# hb100_smd.net
KiCad netlist of a schematic drawn in EAGLE
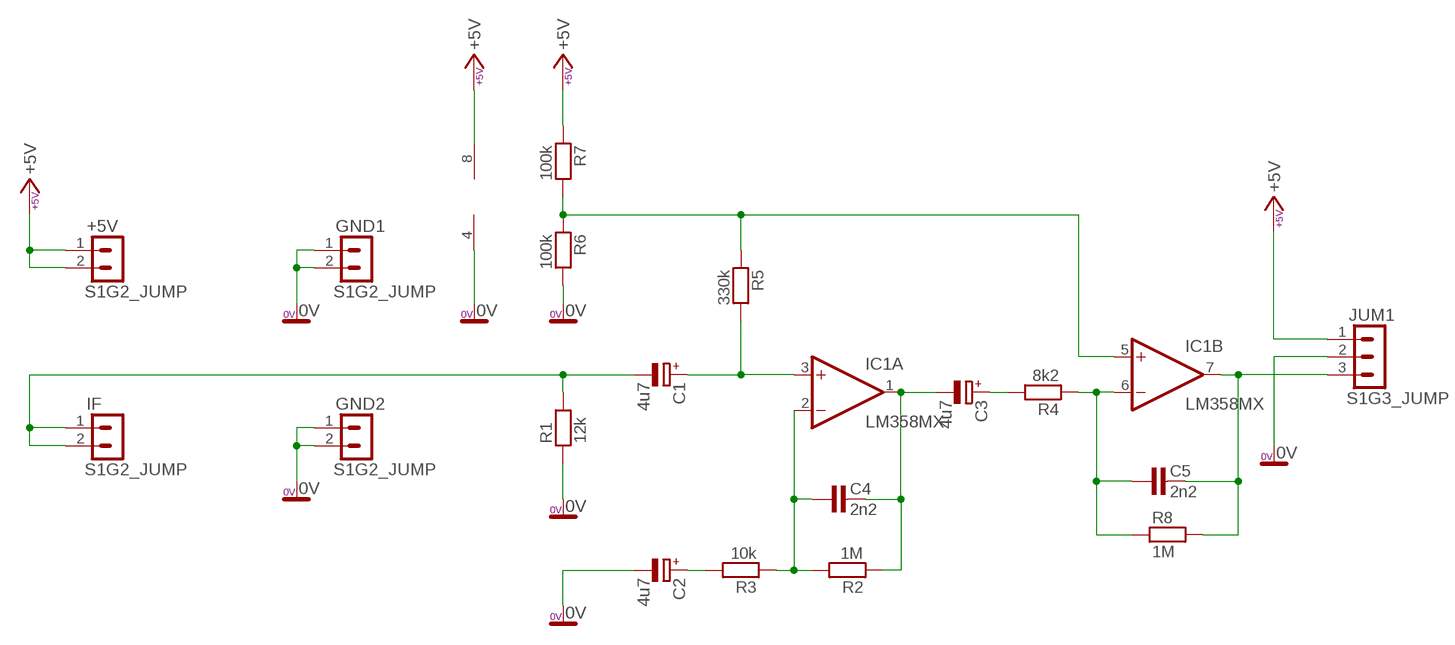
[diagram p0: schematic, sheet 1]

(export (version "E")
  (design (tool "Eeschema 10.0.6"))
  (components
    (comp (ref "+5V")
      (value "S1G2_JUMP")
      (footprint "eagle-import:S1G2_JUM")
      (libsource (lib "eagle-import") (part "S1G2_JUMP"))
    )
    (comp (ref "C1")
      (value "4u7")
      (footprint "eagle-import:SMC_A")
      (libsource (lib "eagle-import") (part "CPOL-EUSMCA"))
    )
    (comp (ref "C2")
      (value "4u7")
      (footprint "eagle-import:SMC_A")
      (libsource (lib "eagle-import") (part "CPOL-EUSMCA"))
    )
    (comp (ref "C3")
      (value "4u7")
      (footprint "eagle-import:SMC_A")
      (libsource (lib "eagle-import") (part "CPOL-EUSMCA"))
    )
    (comp (ref "C4")
      (value "2n2")
      (footprint "eagle-import:0805")
      (libsource (lib "eagle-import") (part "C-KERAMIK_SMD_0805"))
    )
    (comp (ref "C5")
      (value "2n2")
      (footprint "eagle-import:0805")
      (libsource (lib "eagle-import") (part "C-KERAMIK_SMD_0805"))
    )
    (comp (ref "GND1")
      (value "S1G2_JUMP")
      (footprint "eagle-import:S1G2_JUM")
      (libsource (lib "eagle-import") (part "S1G2_JUMP"))
    )
    (comp (ref "GND2")
      (value "S1G2_JUMP")
      (footprint "eagle-import:S1G2_JUM")
      (libsource (lib "eagle-import") (part "S1G2_JUMP"))
    )
    (comp (ref "IC1")
      (value "LM358MX")
      (footprint "eagle-import:SO08")
      (libsource (lib "eagle-import") (part "LM358MX"))
    )
    (comp (ref "IF")
      (value "S1G2_JUMP")
      (footprint "eagle-import:S1G2_JUM")
      (libsource (lib "eagle-import") (part "S1G2_JUMP"))
    )
    (comp (ref "JUM1")
      (value "S1G3_JUMP")
      (footprint "eagle-import:S1G3_JUM")
      (libsource (lib "eagle-import") (part "S1G3_JUMP"))
    )
    (comp (ref "R1")
      (value "12k")
      (footprint "eagle-import:0805")
      (libsource (lib "eagle-import") (part "R_SMD_0805"))
    )
    (comp (ref "R2")
      (value "1M")
      (footprint "eagle-import:0805")
      (libsource (lib "eagle-import") (part "R_SMD_0805"))
    )
    (comp (ref "R3")
      (value "10k")
      (footprint "eagle-import:0805")
      (libsource (lib "eagle-import") (part "R_SMD_0805"))
    )
    (comp (ref "R4")
      (value "8k2")
      (footprint "eagle-import:0805")
      (libsource (lib "eagle-import") (part "R_SMD_0805"))
    )
    (comp (ref "R5")
      (value "330k")
      (footprint "eagle-import:0805")
      (libsource (lib "eagle-import") (part "R_SMD_0805"))
    )
    (comp (ref "R6")
      (value "100k")
      (footprint "eagle-import:0805")
      (libsource (lib "eagle-import") (part "R_SMD_0805"))
    )
    (comp (ref "R7")
      (value "100k")
      (footprint "eagle-import:0805")
      (libsource (lib "eagle-import") (part "R_SMD_0805"))
    )
    (comp (ref "R8")
      (value "1M")
      (footprint "eagle-import:0805")
      (libsource (lib "eagle-import") (part "R_SMD_0805"))
    )
  )
  (nets
    (net (code "1") (name "+5V") (class "Default")
      (node (ref "+5V") (pin "1") (pinfunction "1_1") (pintype "passive"))
      (node (ref "+5V") (pin "2") (pinfunction "2_2") (pintype "passive"))
      (node (ref "IC1") (pin "8") (pinfunction "V+_8") (pintype "power_in"))
      (node (ref "JUM1") (pin "1") (pinfunction "1_1") (pintype "passive"))
      (node (ref "R7") (pin "1") (pinfunction "1_1") (pintype "passive"))
    )
    (net (code "2") (name "0V") (class "Default")
      (node (ref "C2") (pin "-") (pinfunction "-_-") (pintype "passive"))
      (node (ref "GND1") (pin "1") (pinfunction "1_1") (pintype "passive"))
      (node (ref "GND1") (pin "2") (pinfunction "2_2") (pintype "passive"))
      (node (ref "GND2") (pin "1") (pinfunction "1_1") (pintype "passive"))
      (node (ref "GND2") (pin "2") (pinfunction "2_2") (pintype "passive"))
      (node (ref "IC1") (pin "4") (pinfunction "V-_4") (pintype "power_in"))
      (node (ref "JUM1") (pin "2") (pinfunction "2_2") (pintype "passive"))
      (node (ref "R1") (pin "1") (pinfunction "1_1") (pintype "passive"))
      (node (ref "R6") (pin "2") (pinfunction "2_2") (pintype "passive"))
    )
    (net (code "3") (name "Net-(C1-Pad-)") (class "Default")
      (node (ref "C1") (pin "-") (pinfunction "-_-") (pintype "passive"))
      (node (ref "IF") (pin "1") (pinfunction "1_1") (pintype "passive"))
      (node (ref "IF") (pin "2") (pinfunction "2_2") (pintype "passive"))
      (node (ref "R1") (pin "2") (pinfunction "2_2") (pintype "passive"))
    )
    (net (code "4") (name "Net-(C2-Pad+)") (class "Default")
      (node (ref "C2") (pin "+") (pinfunction "+_+") (pintype "passive"))
      (node (ref "R3") (pin "2") (pinfunction "2_2") (pintype "passive"))
    )
    (net (code "5") (name "Net-(C3-Pad+)") (class "Default")
      (node (ref "C3") (pin "+") (pinfunction "+_+") (pintype "passive"))
      (node (ref "R4") (pin "2") (pinfunction "2_2") (pintype "passive"))
    )
    (net (code "6") (name "Net-(IC1A-+IN)") (class "Default")
      (node (ref "C1") (pin "+") (pinfunction "+_+") (pintype "passive"))
      (node (ref "IC1") (pin "3") (pinfunction "+IN_3") (pintype "input"))
      (node (ref "R5") (pin "2") (pinfunction "2_2") (pintype "passive"))
    )
    (net (code "7") (name "Net-(IC1A--IN)") (class "Default")
      (node (ref "C4") (pin "1") (pinfunction "1_1") (pintype "passive"))
      (node (ref "IC1") (pin "2") (pinfunction "-IN_2") (pintype "input"))
      (node (ref "R2") (pin "2") (pinfunction "2_2") (pintype "passive"))
      (node (ref "R3") (pin "1") (pinfunction "1_1") (pintype "passive"))
    )
    (net (code "8") (name "Net-(IC1A-OUT)") (class "Default")
      (node (ref "C3") (pin "-") (pinfunction "-_-") (pintype "passive"))
      (node (ref "C4") (pin "2") (pinfunction "2_2") (pintype "passive"))
      (node (ref "IC1") (pin "1") (pinfunction "OUT_1") (pintype "output"))
      (node (ref "R2") (pin "1") (pinfunction "1_1") (pintype "passive"))
    )
    (net (code "9") (name "Net-(IC1B-+IN)") (class "Default")
      (node (ref "IC1") (pin "5") (pinfunction "+IN_5") (pintype "input"))
      (node (ref "R5") (pin "1") (pinfunction "1_1") (pintype "passive"))
      (node (ref "R6") (pin "1") (pinfunction "1_1") (pintype "passive"))
      (node (ref "R7") (pin "2") (pinfunction "2_2") (pintype "passive"))
    )
    (net (code "10") (name "Net-(IC1B--IN)") (class "Default")
      (node (ref "C5") (pin "1") (pinfunction "1_1") (pintype "passive"))
      (node (ref "IC1") (pin "6") (pinfunction "-IN_6") (pintype "input"))
      (node (ref "R4") (pin "1") (pinfunction "1_1") (pintype "passive"))
      (node (ref "R8") (pin "1") (pinfunction "1_1") (pintype "passive"))
    )
    (net (code "11") (name "Net-(IC1B-OUT)") (class "Default")
      (node (ref "C5") (pin "2") (pinfunction "2_2") (pintype "passive"))
      (node (ref "IC1") (pin "7") (pinfunction "OUT_7") (pintype "output"))
      (node (ref "JUM1") (pin "3") (pinfunction "3_3") (pintype "passive"))
      (node (ref "R8") (pin "2") (pinfunction "2_2") (pintype "passive"))
    )
  )
)
